# 05_-USB_C_MUX_Interface.net
KiCad netlist of a schematic drawn in Altium Designer
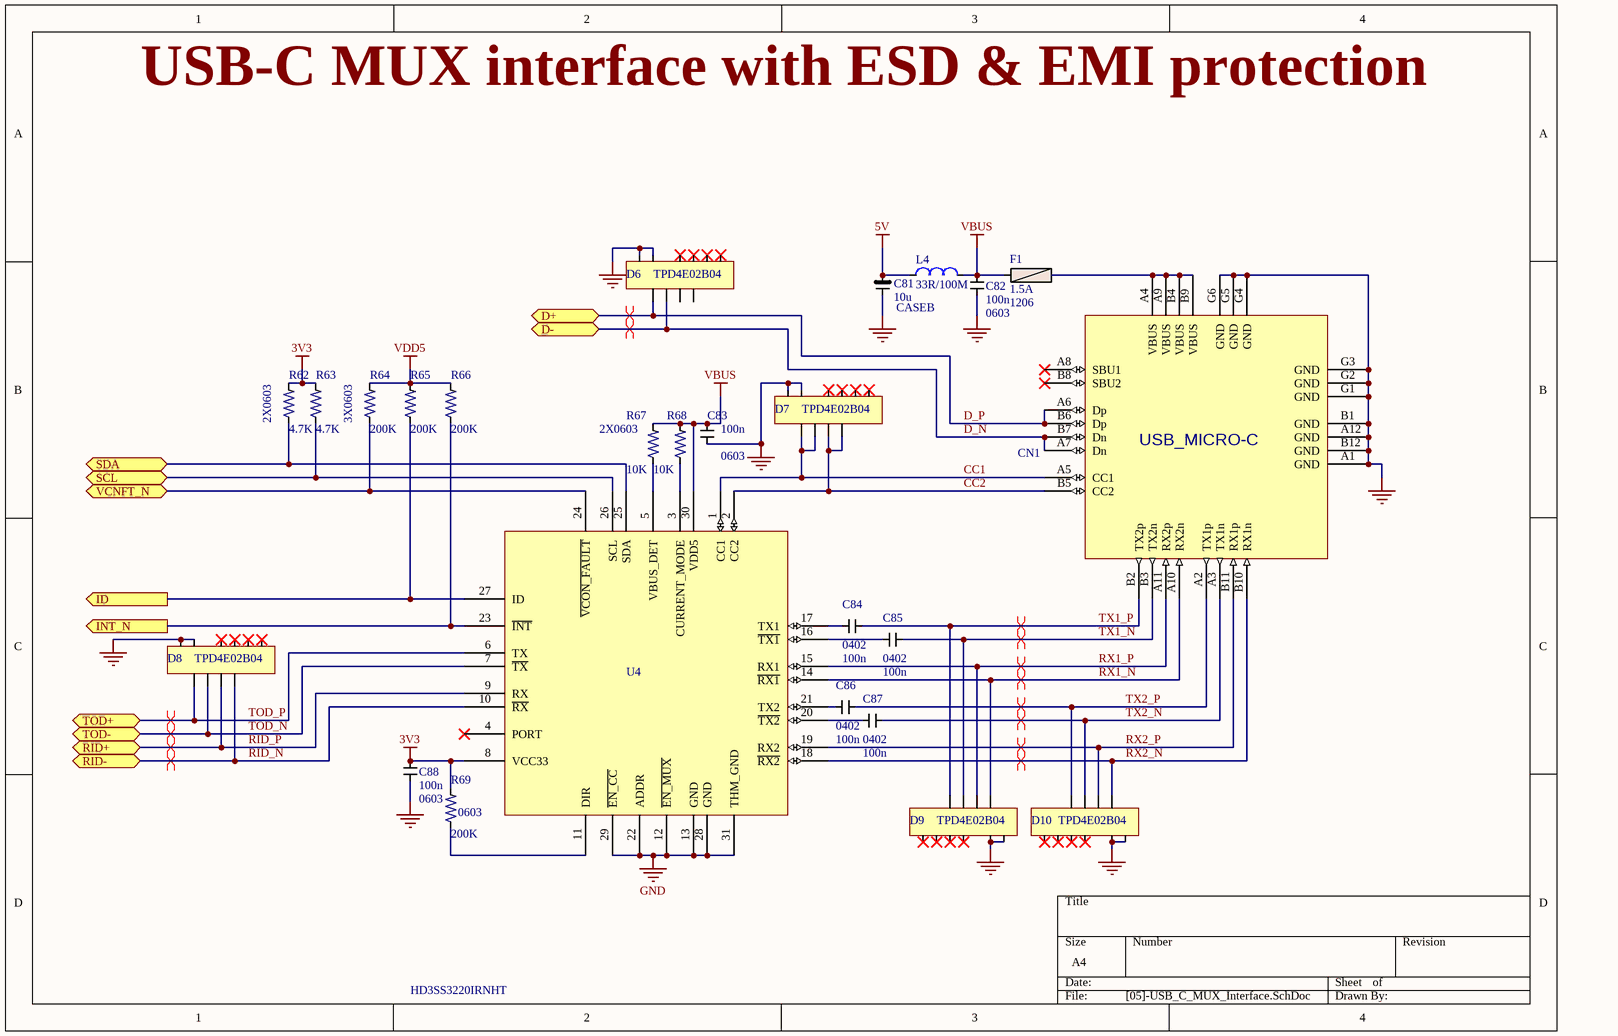
[diagram p0: [05]-USB_C_MUX_Interface.SchDoc]

(export (version "E")
  (design (tool "Eeschema 10.0.6"))
  (components
    (comp (ref "C81")
      (value "10u")
      (footprint "CAPC3528X21N")
      (fields (field (name "PCB LAYER") "CASEB"))
      (libsource (lib "T495B106K010ATE600") (part "Component_1"))
    )
    (comp (ref "C82")
      (value "100n")
      (fields (field (name "PCB FOOTPRINT") "0603"))
      (libsource (lib "06031C104KAT2A") (part "Component_1"))
    )
    (comp (ref "C83")
      (value "100n")
      (fields (field (name "PCB FOOTPRINT") "0603"))
      (libsource (lib "06031C104KAT2A") (part "Component_1"))
    )
    (comp (ref "C84")
      (value "100n")
      (footprint "*CAPC1005X60N")
      (fields (field (name "PCB STAKE") "0402"))
      (libsource (lib "04023C104KAT2A_0402") (part "Component_1"))
    )
    (comp (ref "C85")
      (value "100n")
      (footprint "*CAPC1005X60N")
      (fields (field (name "PCB STAKE") "0402"))
      (libsource (lib "04023C104KAT2A_0402") (part "Component_1"))
    )
    (comp (ref "C86")
      (value "100n")
      (footprint "*CAPC1005X60N")
      (fields (field (name "PCB STAKE") "0402"))
      (libsource (lib "04023C104KAT2A_0402") (part "Component_1"))
    )
    (comp (ref "C87")
      (value "100n")
      (footprint "*CAPC1005X60N")
      (fields (field (name "PCB STAKE") "0402"))
      (libsource (lib "04023C104KAT2A_0402") (part "Component_1"))
    )
    (comp (ref "C88")
      (value "100n")
      (fields (field (name "PCB FOOTPRINT") "0603"))
      (libsource (lib "06031C104KAT2A") (part "Component_1"))
    )
    (comp (ref "CN1")
      (value "USB_MICRO-C")
      (footprint "PCBComponent_1 - duplicate1")
      (description "Connector USB Type C RCP SMD 24 Terminal workable with USB 3.1,3.0 and 2.0 standards.")
      (fields
        (field (name "MP") "1-2295018-2")
        (field (name "MF") "TE Connectivity")
        (field (name "DESIGNED BY") "Faheem Minhas")
      )
      (libsource (lib "MICRO_C_USB") (part "1-2295018-2"))
    )
    (comp (ref "D6") (value "TPD4E02B04") (libsource (lib "TPD4E02B04") (part "Component_1")))
    (comp (ref "D7") (value "TPD4E02B04") (libsource (lib "TPD4E02B04") (part "Component_1")))
    (comp (ref "D8")
      (value "TPD4E02B04")
      (footprint "TI_TPD4E05U06DQAR")
      (libsource (lib "TPD4E02B04") (part "Component_1"))
    )
    (comp (ref "D9")
      (value "TPD4E02B04")
      (footprint "TI_TPD4E05U06DQAR")
      (libsource (lib "") (part "Component_1_1"))
    )
    (comp (ref "D10")
      (value "TPD4E02B04")
      (footprint "TI_TPD4E05U06DQAR")
      (libsource (lib "") (part "Component_1_1"))
    )
    (comp (ref "F1")
      (value "1.5A")
      (footprint "*CAP3216X125N")
      (fields (field (name "PCB TYPE") "1206"))
      (libsource (lib "BLM31PG601SN1L") (part "Component_1"))
    )
    (comp (ref "L4")
      (value "33R/100M")
      (footprint "*FB_BLM18PG121SN1D")
      (libsource (lib "BLM18PG330SN1D") (part "Component_1"))
    )
    (comp (ref "R62")
      (value "4.7K")
      (footprint "*RESC1608X50N")
      (description "Res Thin Film 0603 76.8 Ohm 0.1% 1/10W Â±15ppm/Â°C Molded SMD Paper T/R")
      (fields
        (field (name "MP") "RP73D1J76R8BTDG")
        (field (name "MF") "TE Connectivity / Holsworthy")
        (field (name "FOOT PRINT") "2X0603")
      )
      (libsource (lib "CRGH0603F4K7") (part "RP73D1J76R8BTDG"))
    )
    (comp (ref "R63")
      (value "4.7K")
      (footprint "*RESC1608X50N")
      (description "Res Thin Film 0603 76.8 Ohm 0.1% 1/10W Â±15ppm/Â°C Molded SMD Paper T/R")
      (fields (field (name "MP") "RP73D1J76R8BTDG") (field (name "MF") "TE Connectivity / Holsworthy"))
      (libsource (lib "CRGH0603F4K7") (part "RP73D1J76R8BTDG"))
    )
    (comp (ref "R64")
      (value "200K")
      (footprint "*RESC1608X60N")
      (description "Res Thin Film 0603 76.8 Ohm 0.1% 1/10W Â±15ppm/Â°C Molded SMD Paper T/R")
      (fields
        (field (name "MP") "RP73D1J76R8BTDG")
        (field (name "MF") "TE Connectivity / Holsworthy")
        (field (name "FOOT PRINT") "3X0603")
      )
      (libsource (lib "CRCW0603200KFKEA") (part "RP73D1J76R8BTDG"))
    )
    (comp (ref "R65")
      (value "200K")
      (footprint "*RESC1608X60N")
      (description "Res Thin Film 0603 76.8 Ohm 0.1% 1/10W Â±15ppm/Â°C Molded SMD Paper T/R")
      (fields (field (name "MP") "RP73D1J76R8BTDG") (field (name "MF") "TE Connectivity / Holsworthy"))
      (libsource (lib "CRCW0603200KFKEA") (part "RP73D1J76R8BTDG"))
    )
    (comp (ref "R66")
      (value "200K")
      (footprint "*RESC1608X60N")
      (description "Res Thin Film 0603 76.8 Ohm 0.1% 1/10W Â±15ppm/Â°C Molded SMD Paper T/R")
      (fields (field (name "MP") "RP73D1J76R8BTDG") (field (name "MF") "TE Connectivity / Holsworthy"))
      (libsource (lib "CRCW0603200KFKEA") (part "RP73D1J76R8BTDG"))
    )
    (comp (ref "R67")
      (value "10K")
      (footprint "*0603")
      (description "Res Thin Film 0603 76.8 Ohm 0.1% 1/10W Â±15ppm/Â°C Molded SMD Paper T/R")
      (fields
        (field (name "MP") "RP73D1J76R8BTDG")
        (field (name "MF") "TE Connectivity / Holsworthy")
        (field (name "FOOT PRINT") "2X0603")
      )
      (libsource (lib "CRCW060310K0FKEAHP") (part "RP73D1J76R8BTDG"))
    )
    (comp (ref "R68")
      (value "10K")
      (footprint "*0603")
      (description "Res Thin Film 0603 76.8 Ohm 0.1% 1/10W Â±15ppm/Â°C Molded SMD Paper T/R")
      (fields (field (name "MP") "RP73D1J76R8BTDG") (field (name "MF") "TE Connectivity / Holsworthy"))
      (libsource (lib "CRCW060310K0FKEAHP") (part "RP73D1J76R8BTDG"))
    )
    (comp (ref "R69")
      (value "200K")
      (footprint "*RESC1608X60N")
      (description "Res Thin Film 0603 76.8 Ohm 0.1% 1/10W Â±15ppm/Â°C Molded SMD Paper T/R")
      (fields
        (field (name "MP") "RP73D1J76R8BTDG")
        (field (name "MF") "TE Connectivity / Holsworthy")
        (field (name "FOOT PRINT") "0603")
      )
      (libsource (lib "CRCW0603200KFKEA") (part "RP73D1J76R8BTDG"))
    )
    (comp (ref "U4")
      (value "HD3SS3220IRNHT")
      (footprint "QFN40P450X250X80-31N120X320")
      (description "Super Speed Type-C DRP Port Controller USB 3.1 3.3V/5V T/R 30-Pin WQFN EP")
      (fields (field (name "MF") "Texas Instruments"))
      (libsource (lib "HD3SS3220IRNHT") (part "HD3SS3220IRNHT"))
    )
  )
  (nets
    (net (code "1") (name "/CC1") (class "Default")
      (node (ref "CN1") (pin "A5") (pinfunction "CC1_A5") (pintype "bidirectional"))
      (node (ref "D7") (pin "1") (pinfunction "IO1_1") (pintype "passive"))
      (node (ref "D7") (pin "2") (pinfunction "IO2_2") (pintype "passive"))
      (node (ref "U4") (pin "1") (pinfunction "CC1_1") (pintype "bidirectional"))
    )
    (net (code "2") (name "/CC2") (class "Default")
      (node (ref "CN1") (pin "B5") (pinfunction "CC2_B5") (pintype "bidirectional"))
      (node (ref "D7") (pin "4") (pinfunction "IO3_4") (pintype "passive"))
      (node (ref "D7") (pin "5") (pinfunction "IO4_5") (pintype "passive"))
      (node (ref "U4") (pin "2") (pinfunction "CC2_2") (pintype "bidirectional"))
    )
    (net (code "3") (name "/D_N") (class "Default")
      (node (ref "CN1") (pin "A7") (pinfunction "Dn_A7") (pintype "bidirectional"))
      (node (ref "CN1") (pin "B7") (pinfunction "Dn_B7") (pintype "bidirectional"))
      (node (ref "D6") (pin "2") (pinfunction "IO2_2") (pintype "passive"))
    )
    (net (code "4") (name "/D_P") (class "Default")
      (node (ref "CN1") (pin "A6") (pinfunction "Dp_A6") (pintype "bidirectional"))
      (node (ref "CN1") (pin "B6") (pinfunction "Dp_B6") (pintype "bidirectional"))
      (node (ref "D6") (pin "1") (pinfunction "IO1_1") (pintype "passive"))
    )
    (net (code "5") (name "/ID") (class "Default")
      (node (ref "R65") (pin "1") (pinfunction "1_1") (pintype "passive"))
      (node (ref "U4") (pin "27") (pinfunction "ID_27") (pintype "passive"))
    )
    (net (code "6") (name "/INT_N") (class "Default")
      (node (ref "R66") (pin "1") (pinfunction "1_1") (pintype "passive"))
      (node (ref "U4") (pin "23") (pinfunction "~{INT}_23") (pintype "passive"))
    )
    (net (code "7") (name "/RID_N") (class "Default")
      (node (ref "D8") (pin "5") (pinfunction "IO4_5") (pintype "passive"))
      (node (ref "U4") (pin "10") (pinfunction "~{RX}_10") (pintype "passive"))
    )
    (net (code "8") (name "/RID_P") (class "Default")
      (node (ref "D8") (pin "4") (pinfunction "IO3_4") (pintype "passive"))
      (node (ref "U4") (pin "9") (pinfunction "RX_9") (pintype "passive"))
    )
    (net (code "9") (name "/RX1_N") (class "Default")
      (node (ref "CN1") (pin "A10") (pinfunction "RX2n_A10") (pintype "input"))
      (node (ref "D9") (pin "1") (pinfunction "IO1_1") (pintype "passive"))
      (node (ref "U4") (pin "14") (pinfunction "~{RX1}_14") (pintype "bidirectional"))
    )
    (net (code "10") (name "/RX1_P") (class "Default")
      (node (ref "CN1") (pin "A11") (pinfunction "RX2p_A11") (pintype "input"))
      (node (ref "D9") (pin "2") (pinfunction "IO2_2") (pintype "passive"))
      (node (ref "U4") (pin "15") (pinfunction "RX1_15") (pintype "bidirectional"))
    )
    (net (code "11") (name "/RX2_N") (class "Default")
      (node (ref "CN1") (pin "B10") (pinfunction "RX1n_B10") (pintype "input"))
      (node (ref "D10") (pin "1") (pinfunction "IO1_1") (pintype "passive"))
      (node (ref "U4") (pin "18") (pinfunction "~{RX2}_18") (pintype "bidirectional"))
    )
    (net (code "12") (name "/RX2_P") (class "Default")
      (node (ref "CN1") (pin "B11") (pinfunction "RX1p_B11") (pintype "input"))
      (node (ref "D10") (pin "2") (pinfunction "IO2_2") (pintype "passive"))
      (node (ref "U4") (pin "19") (pinfunction "RX2_19") (pintype "bidirectional"))
    )
    (net (code "13") (name "/SCL") (class "Default")
      (node (ref "R63") (pin "1") (pinfunction "1_1") (pintype "passive"))
      (node (ref "U4") (pin "26") (pinfunction "SCL_26") (pintype "passive"))
    )
    (net (code "14") (name "/SDA") (class "Default")
      (node (ref "R62") (pin "1") (pinfunction "1_1") (pintype "passive"))
      (node (ref "U4") (pin "25") (pinfunction "SDA_25") (pintype "passive"))
    )
    (net (code "15") (name "/TOD_N") (class "Default")
      (node (ref "D8") (pin "2") (pinfunction "IO2_2") (pintype "passive"))
      (node (ref "U4") (pin "7") (pinfunction "~{TX}_7") (pintype "passive"))
    )
    (net (code "16") (name "/TOD_P") (class "Default")
      (node (ref "D8") (pin "1") (pinfunction "IO1_1") (pintype "passive"))
      (node (ref "U4") (pin "6") (pinfunction "TX_6") (pintype "passive"))
    )
    (net (code "17") (name "/TX1_N") (class "Default")
      (node (ref "C85") (pin "1") (pinfunction "1_1") (pintype "passive"))
      (node (ref "CN1") (pin "B3") (pinfunction "TX2n_B3") (pintype "output"))
      (node (ref "D9") (pin "4") (pinfunction "IO3_4") (pintype "passive"))
    )
    (net (code "18") (name "/TX1_P") (class "Default")
      (node (ref "C84") (pin "1") (pinfunction "1_1") (pintype "passive"))
      (node (ref "CN1") (pin "B2") (pinfunction "TX2p_B2") (pintype "output"))
      (node (ref "D9") (pin "5") (pinfunction "IO4_5") (pintype "passive"))
    )
    (net (code "19") (name "/TX2_N") (class "Default")
      (node (ref "C87") (pin "1") (pinfunction "1_1") (pintype "passive"))
      (node (ref "CN1") (pin "A3") (pinfunction "TX1n_A3") (pintype "output"))
      (node (ref "D10") (pin "4") (pinfunction "IO3_4") (pintype "passive"))
    )
    (net (code "20") (name "/TX2_P") (class "Default")
      (node (ref "C86") (pin "1") (pinfunction "1_1") (pintype "passive"))
      (node (ref "CN1") (pin "A2") (pinfunction "TX1p_A2") (pintype "output"))
      (node (ref "D10") (pin "5") (pinfunction "IO4_5") (pintype "passive"))
    )
    (net (code "21") (name "/VCNFT_N") (class "Default")
      (node (ref "R64") (pin "1") (pinfunction "1_1") (pintype "passive"))
      (node (ref "U4") (pin "24") (pinfunction "~{VCON_FAULT}_24") (pintype "passive"))
    )
    (net (code "22") (name "3V3") (class "Default")
      (node (ref "C88") (pin "2") (pinfunction "2_2") (pintype "passive"))
      (node (ref "R62") (pin "2") (pinfunction "2_2") (pintype "passive"))
      (node (ref "R63") (pin "2") (pinfunction "2_2") (pintype "passive"))
      (node (ref "R69") (pin "2") (pinfunction "2_2") (pintype "passive"))
      (node (ref "U4") (pin "8") (pinfunction "VCC33_8") (pintype "power_in"))
    )
    (net (code "23") (name "5V") (class "Default")
      (node (ref "C81") (pin "1") (pinfunction "1_1") (pintype "passive"))
      (node (ref "L4") (pin "1") (pinfunction "1_1") (pintype "passive"))
    )
    (net (code "24") (name "GND") (class "Default")
      (node (ref "C81") (pin "2") (pinfunction "2_2") (pintype "passive"))
      (node (ref "C82") (pin "1") (pinfunction "1_1") (pintype "passive"))
      (node (ref "C83") (pin "1") (pinfunction "1_1") (pintype "passive"))
      (node (ref "C88") (pin "1") (pinfunction "1_1") (pintype "passive"))
      (node (ref "CN1") (pin "A1") (pinfunction "GND_A1") (pintype "power_in"))
      (node (ref "CN1") (pin "A12") (pinfunction "GND_A12") (pintype "power_in"))
      (node (ref "CN1") (pin "B1") (pinfunction "GND_B1") (pintype "power_in"))
      (node (ref "CN1") (pin "B12") (pinfunction "GND_B12") (pintype "power_in"))
      (node (ref "CN1") (pin "G1") (pinfunction "GND_G1") (pintype "passive"))
      (node (ref "CN1") (pin "G2") (pinfunction "GND_G2") (pintype "passive"))
      (node (ref "CN1") (pin "G3") (pinfunction "GND_G3") (pintype "passive"))
      (node (ref "CN1") (pin "G4") (pinfunction "GND_G4") (pintype "passive"))
      (node (ref "CN1") (pin "G5") (pinfunction "GND_G5") (pintype "passive"))
      (node (ref "CN1") (pin "G6") (pinfunction "GND_G6") (pintype "passive"))
      (node (ref "D10") (pin "3") (pinfunction "GND_3") (pintype "power_in"))
      (node (ref "D10") (pin "8") (pinfunction "GND_8") (pintype "power_in"))
      (node (ref "D6") (pin "3") (pinfunction "GND_3") (pintype "power_in"))
      (node (ref "D6") (pin "8") (pinfunction "GND_8") (pintype "power_in"))
      (node (ref "D7") (pin "3") (pinfunction "GND_3") (pintype "power_in"))
      (node (ref "D7") (pin "8") (pinfunction "GND_8") (pintype "power_in"))
      (node (ref "D8") (pin "3") (pinfunction "GND_3") (pintype "power_in"))
      (node (ref "D8") (pin "8") (pinfunction "GND_8") (pintype "power_in"))
      (node (ref "D9") (pin "3") (pinfunction "GND_3") (pintype "power_in"))
      (node (ref "D9") (pin "8") (pinfunction "GND_8") (pintype "power_in"))
      (node (ref "U4") (pin "12") (pinfunction "~{EN_MUX}_12") (pintype "passive"))
      (node (ref "U4") (pin "13") (pinfunction "GND_13") (pintype "power_in"))
      (node (ref "U4") (pin "22") (pinfunction "ADDR_22") (pintype "passive"))
      (node (ref "U4") (pin "28") (pinfunction "GND_28") (pintype "power_in"))
      (node (ref "U4") (pin "29") (pinfunction "~{EN_CC}_29") (pintype "passive"))
      (node (ref "U4") (pin "31") (pinfunction "THM_GND_31") (pintype "power_in"))
    )
    (net (code "25") (name "Net-(CN1-VBUS-PadA4)") (class "Default")
      (node (ref "CN1") (pin "A4") (pinfunction "VBUS_A4") (pintype "power_in"))
      (node (ref "CN1") (pin "A9") (pinfunction "VBUS_A9") (pintype "power_in"))
      (node (ref "CN1") (pin "B4") (pinfunction "VBUS_B4") (pintype "power_in"))
      (node (ref "CN1") (pin "B9") (pinfunction "VBUS_B9") (pintype "power_in"))
      (node (ref "F1") (pin "2") (pinfunction "2_2") (pintype "passive"))
    )
    (net (code "26") (name "Net-(U4-CURRENT_MODE)") (class "Default")
      (node (ref "R68") (pin "1") (pinfunction "1_1") (pintype "passive"))
      (node (ref "U4") (pin "3") (pinfunction "CURRENT_MODE_3") (pintype "passive"))
    )
    (net (code "27") (name "Net-(U4-DIR)") (class "Default")
      (node (ref "R69") (pin "1") (pinfunction "1_1") (pintype "passive"))
      (node (ref "U4") (pin "11") (pinfunction "DIR_11") (pintype "passive"))
    )
    (net (code "28") (name "Net-(U4-TX1)") (class "Default")
      (node (ref "C84") (pin "2") (pinfunction "2_2") (pintype "passive"))
      (node (ref "U4") (pin "17") (pinfunction "TX1_17") (pintype "bidirectional"))
    )
    (net (code "29") (name "Net-(U4-TX2)") (class "Default")
      (node (ref "C86") (pin "2") (pinfunction "2_2") (pintype "passive"))
      (node (ref "U4") (pin "21") (pinfunction "TX2_21") (pintype "bidirectional"))
    )
    (net (code "30") (name "Net-(U4-VBUS_DET)") (class "Default")
      (node (ref "R67") (pin "1") (pinfunction "1_1") (pintype "passive"))
      (node (ref "U4") (pin "5") (pinfunction "VBUS_DET_5") (pintype "passive"))
    )
    (net (code "31") (name "Net-(U4-~{TX1})") (class "Default")
      (node (ref "C85") (pin "2") (pinfunction "2_2") (pintype "passive"))
      (node (ref "U4") (pin "16") (pinfunction "~{TX1}_16") (pintype "bidirectional"))
    )
    (net (code "32") (name "Net-(U4-~{TX2})") (class "Default")
      (node (ref "C87") (pin "2") (pinfunction "2_2") (pintype "passive"))
      (node (ref "U4") (pin "20") (pinfunction "~{TX2}_20") (pintype "bidirectional"))
    )
    (net (code "33") (name "VBUS") (class "Default")
      (node (ref "C82") (pin "2") (pinfunction "2_2") (pintype "passive"))
      (node (ref "C83") (pin "2") (pinfunction "2_2") (pintype "passive"))
      (node (ref "F1") (pin "1") (pinfunction "1_1") (pintype "passive"))
      (node (ref "L4") (pin "2") (pinfunction "2_2") (pintype "passive"))
      (node (ref "R67") (pin "2") (pinfunction "2_2") (pintype "passive"))
      (node (ref "R68") (pin "2") (pinfunction "2_2") (pintype "passive"))
      (node (ref "U4") (pin "30") (pinfunction "VDD5_30") (pintype "power_in"))
    )
    (net (code "34") (name "VDD5") (class "Default")
      (node (ref "R64") (pin "2") (pinfunction "2_2") (pintype "passive"))
      (node (ref "R65") (pin "2") (pinfunction "2_2") (pintype "passive"))
      (node (ref "R66") (pin "2") (pinfunction "2_2") (pintype "passive"))
    )
    (net (code "35") (name "unconnected-(CN1-SBU1-PadA8)") (class "Default")
      (node (ref "CN1") (pin "A8") (pinfunction "SBU1_A8") (pintype "bidirectional+no_connect"))
    )
    (net (code "36") (name "unconnected-(CN1-SBU2-PadB8)") (class "Default")
      (node (ref "CN1") (pin "B8") (pinfunction "SBU2_B8") (pintype "bidirectional+no_connect"))
    )
    (net (code "37") (name "unconnected-(D6-IO3-Pad4)") (class "Default")
      (node (ref "D6") (pin "4") (pinfunction "IO3_4") (pintype "passive"))
    )
    (net (code "38") (name "unconnected-(D6-IO4-Pad5)") (class "Default")
      (node (ref "D6") (pin "5") (pinfunction "IO4_5") (pintype "passive"))
    )
    (net (code "39") (name "unconnected-(D6-NC-Pad6)") (class "Default")
      (node (ref "D6") (pin "6") (pinfunction "NC_6") (pintype "open_emitter+no_connect"))
    )
    (net (code "40") (name "unconnected-(D6-NC-Pad7)") (class "Default")
      (node (ref "D6") (pin "7") (pinfunction "NC_7") (pintype "open_emitter+no_connect"))
    )
    (net (code "41") (name "unconnected-(D6-NC-Pad9)") (class "Default")
      (node (ref "D6") (pin "9") (pinfunction "NC_9") (pintype "open_emitter+no_connect"))
    )
    (net (code "42") (name "unconnected-(D6-NC-Pad10)") (class "Default")
      (node (ref "D6") (pin "10") (pinfunction "NC_10") (pintype "open_emitter+no_connect"))
    )
    (net (code "43") (name "unconnected-(D7-NC-Pad6)") (class "Default")
      (node (ref "D7") (pin "6") (pinfunction "NC_6") (pintype "open_emitter+no_connect"))
    )
    (net (code "44") (name "unconnected-(D7-NC-Pad7)") (class "Default")
      (node (ref "D7") (pin "7") (pinfunction "NC_7") (pintype "open_emitter+no_connect"))
    )
    (net (code "45") (name "unconnected-(D7-NC-Pad9)") (class "Default")
      (node (ref "D7") (pin "9") (pinfunction "NC_9") (pintype "open_emitter+no_connect"))
    )
    (net (code "46") (name "unconnected-(D7-NC-Pad10)") (class "Default")
      (node (ref "D7") (pin "10") (pinfunction "NC_10") (pintype "open_emitter+no_connect"))
    )
    (net (code "47") (name "unconnected-(D8-NC-Pad6)") (class "Default")
      (node (ref "D8") (pin "6") (pinfunction "NC_6") (pintype "open_emitter+no_connect"))
    )
    (net (code "48") (name "unconnected-(D8-NC-Pad7)") (class "Default")
      (node (ref "D8") (pin "7") (pinfunction "NC_7") (pintype "open_emitter+no_connect"))
    )
    (net (code "49") (name "unconnected-(D8-NC-Pad9)") (class "Default")
      (node (ref "D8") (pin "9") (pinfunction "NC_9") (pintype "open_emitter+no_connect"))
    )
    (net (code "50") (name "unconnected-(D8-NC-Pad10)") (class "Default")
      (node (ref "D8") (pin "10") (pinfunction "NC_10") (pintype "open_emitter+no_connect"))
    )
    (net (code "51") (name "unconnected-(D9-NC-Pad6)") (class "Default")
      (node (ref "D9") (pin "6") (pinfunction "NC_6") (pintype "open_emitter+no_connect"))
    )
    (net (code "52") (name "unconnected-(D9-NC-Pad7)") (class "Default")
      (node (ref "D9") (pin "7") (pinfunction "NC_7") (pintype "open_emitter+no_connect"))
    )
    (net (code "53") (name "unconnected-(D9-NC-Pad9)") (class "Default")
      (node (ref "D9") (pin "9") (pinfunction "NC_9") (pintype "open_emitter+no_connect"))
    )
    (net (code "54") (name "unconnected-(D9-NC-Pad10)") (class "Default")
      (node (ref "D9") (pin "10") (pinfunction "NC_10") (pintype "open_emitter+no_connect"))
    )
    (net (code "55") (name "unconnected-(D10-NC-Pad6)") (class "Default")
      (node (ref "D10") (pin "6") (pinfunction "NC_6") (pintype "open_emitter+no_connect"))
    )
    (net (code "56") (name "unconnected-(D10-NC-Pad7)") (class "Default")
      (node (ref "D10") (pin "7") (pinfunction "NC_7") (pintype "open_emitter+no_connect"))
    )
    (net (code "57") (name "unconnected-(D10-NC-Pad9)") (class "Default")
      (node (ref "D10") (pin "9") (pinfunction "NC_9") (pintype "open_emitter+no_connect"))
    )
    (net (code "58") (name "unconnected-(D10-NC-Pad10)") (class "Default")
      (node (ref "D10") (pin "10") (pinfunction "NC_10") (pintype "open_emitter+no_connect"))
    )
    (net (code "59") (name "unconnected-(U4-PORT-Pad4)") (class "Default")
      (node (ref "U4") (pin "4") (pinfunction "PORT_4") (pintype "passive+no_connect"))
    )
  )
)
